# Seed_Laser_Controller.net
KiCad netlist of a schematic drawn in Altium Designer
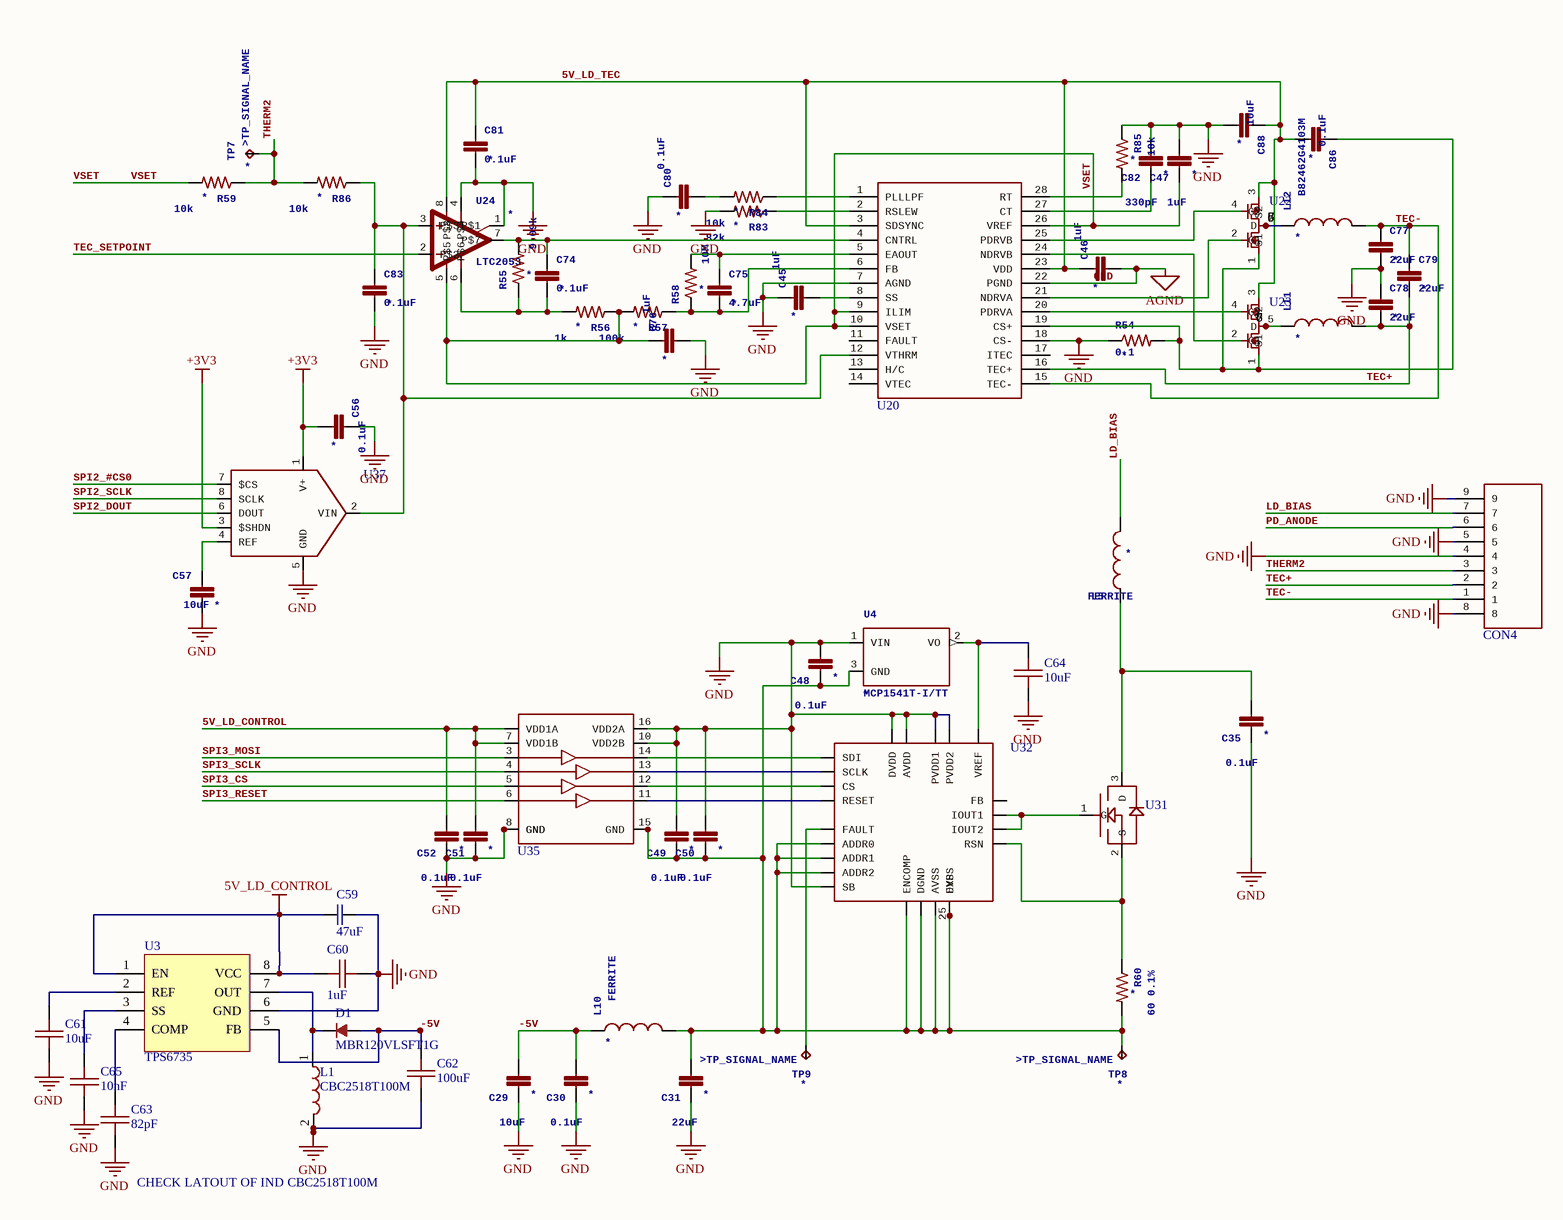
[diagram p0: Seed Laser Controller.SchDoc]

(export (version "E")
  (design (tool "Eeschema 10.0.6"))
  (components
    (comp (ref "C29")
      (value "10uF")
      (footprint "0603")
      (description "CAPACITOR, European symbol")
      (fields (field (name "NAME") "*"))
      (libsource (lib "") (part "C-EUC0603K_1"))
    )
    (comp (ref "C30")
      (value "0.1uF")
      (footprint "0603")
      (description "CAPACITOR, European symbol")
      (fields (field (name "NAME") "*"))
      (libsource (lib "") (part "C-EUC0603K_1"))
    )
    (comp (ref "C31")
      (value "22uF")
      (footprint "0603")
      (description "CAPACITOR, European symbol")
      (fields (field (name "NAME") "*"))
      (libsource (lib "") (part "C-EUC0603K_1"))
    )
    (comp (ref "C35")
      (value "0.1uF")
      (footprint "0603")
      (description "CAPACITOR, European symbol")
      (fields (field (name "NAME") "*"))
      (libsource (lib "") (part "C-EUC0603K_1"))
    )
    (comp (ref "C45")
      (value "1uF")
      (footprint "0402")
      (description "CAPACITOR, European symbol")
      (fields (field (name "NAME") "*"))
      (libsource (lib "rcl") (part "C-EUC0402"))
    )
    (comp (ref "C46")
      (value "1uF")
      (footprint "0402")
      (description "CAPACITOR, European symbol")
      (fields (field (name "NAME") "*"))
      (libsource (lib "rcl") (part "C-EUC0402"))
    )
    (comp (ref "C47")
      (value "1uF")
      (footprint "0402")
      (description "CAPACITOR, European symbol")
      (fields (field (name "NAME") "*"))
      (libsource (lib "") (part "C-EUC0402_1"))
    )
    (comp (ref "C48")
      (value "0.1uF")
      (footprint "0402 B")
      (description "CAPACITOR, European symbol")
      (fields (field (name "NAME") "*"))
      (libsource (lib "") (part "C-EUC0402_1"))
    )
    (comp (ref "C49")
      (value "0.1uF")
      (footprint "0402 B")
      (description "CAPACITOR, European symbol")
      (fields (field (name "NAME") "*"))
      (libsource (lib "") (part "C-EUC0402_1"))
    )
    (comp (ref "C50")
      (value "0.1uF")
      (footprint "0402 B")
      (description "CAPACITOR, European symbol")
      (fields (field (name "NAME") "*"))
      (libsource (lib "") (part "C-EUC0402_1"))
    )
    (comp (ref "C51")
      (value "0.1uF")
      (footprint "0402 B")
      (description "CAPACITOR, European symbol")
      (fields (field (name "NAME") "*"))
      (libsource (lib "") (part "C-EUC0402_1"))
    )
    (comp (ref "C52")
      (value "0.1uF")
      (footprint "0402 B")
      (description "CAPACITOR, European symbol")
      (fields (field (name "NAME") "*"))
      (libsource (lib "") (part "C-EUC0402_1"))
    )
    (comp (ref "C56")
      (value "0.1uF")
      (footprint "0402")
      (description "CAPACITOR, European symbol")
      (fields (field (name "NAME") "*"))
      (libsource (lib "rcl") (part "C-EUC0402K"))
    )
    (comp (ref "C57")
      (value "10uF")
      (footprint "0603")
      (description "CAPACITOR, European symbol")
      (fields (field (name "NAME") "*"))
      (libsource (lib "rcl") (part "C-EUC0603K"))
    )
    (comp (ref "C59") (value "47uF") (footprint "0603") (libsource (lib "DaughterBoard") (part "Cap 0603")))
    (comp (ref "C60")
      (value "1uF")
      (footprint "0402 B")
      (description "402 Capacitor")
      (libsource (lib "DaughterBoard") (part "CAP 0402"))
    )
    (comp (ref "C61")
      (value "10uF")
      (footprint "0402 B")
      (description "402 Capacitor")
      (libsource (lib "DaughterBoard") (part "CAP 0402"))
    )
    (comp (ref "C62")
      (value "100uF")
      (footprint "1206 B")
      (description "1206 Capacitor")
      (libsource (lib "DaughterBoard") (part "CAP 1206"))
    )
    (comp (ref "C63")
      (value "82pF")
      (footprint "0402 B")
      (description "402 Capacitor")
      (libsource (lib "DaughterBoard") (part "CAP 0402"))
    )
    (comp (ref "C64")
      (value "10uF")
      (footprint "0402 B")
      (description "402 Capacitor")
      (libsource (lib "DaughterBoard") (part "CAP 0402"))
    )
    (comp (ref "C65")
      (value "10nF")
      (footprint "0402 B")
      (description "402 Capacitor")
      (libsource (lib "DaughterBoard") (part "CAP 0402"))
    )
    (comp (ref "C74")
      (value "0.1uF")
      (footprint "0603")
      (description "CAPACITOR, European symbol")
      (fields (field (name "NAME") "*"))
      (libsource (lib "rcl") (part "C-EUC0603"))
    )
    (comp (ref "C75")
      (value "4.7uF")
      (footprint "0603")
      (description "CAPACITOR, European symbol")
      (fields (field (name "NAME") "*"))
      (libsource (lib "rcl") (part "C-EUC0603"))
    )
    (comp (ref "C76")
      (value "1uF")
      (footprint "0402")
      (description "CAPACITOR, European symbol")
      (fields (field (name "NAME") "*"))
      (libsource (lib "rcl") (part "C-EUC0402"))
    )
    (comp (ref "C77")
      (value "22uF")
      (footprint "0402")
      (description "CAPACITOR, European symbol")
      (fields (field (name "NAME") "*"))
      (libsource (lib "") (part "C-EUC0402_2"))
    )
    (comp (ref "C78")
      (value "22uF")
      (footprint "0402")
      (description "CAPACITOR, European symbol")
      (fields (field (name "NAME") "*"))
      (libsource (lib "") (part "C-EUC0402_2"))
    )
    (comp (ref "C79")
      (value "22uF")
      (footprint "0603")
      (description "CAPACITOR, European symbol")
      (fields (field (name "NAME") "*"))
      (libsource (lib "rcl") (part "C-EUC0603"))
    )
    (comp (ref "C80")
      (value "0.1uF")
      (footprint "0402")
      (description "CAPACITOR, European symbol")
      (fields (field (name "NAME") "*"))
      (libsource (lib "rcl") (part "C-EUC0402"))
    )
    (comp (ref "C81")
      (value "0.1uF")
      (footprint "0603")
      (description "CAPACITOR, European symbol")
      (fields (field (name "NAME") "*"))
      (libsource (lib "") (part "C-EUC0402_2"))
    )
    (comp (ref "C82")
      (value "330pF")
      (footprint "0402")
      (description "CAPACITOR, European symbol")
      (fields (field (name "NAME") "*"))
      (libsource (lib "") (part "C-EUC0402_1"))
    )
    (comp (ref "C83")
      (value "0.1uF")
      (footprint "0402")
      (description "CAPACITOR, European symbol")
      (fields (field (name "NAME") "*"))
      (libsource (lib "") (part "C-EUC0402_2"))
    )
    (comp (ref "C86")
      (value "0.1uF")
      (footprint "0402")
      (description "CAPACITOR, European symbol")
      (fields (field (name "NAME") "*"))
      (libsource (lib "") (part "C-EUC0402_3"))
    )
    (comp (ref "C88")
      (value "10uF")
      (footprint "0603")
      (description "CAPACITOR, European symbol")
      (fields (field (name "NAME") "*"))
      (libsource (lib "rcl") (part "C-EUC0603K"))
    )
    (comp (ref "CON4")
      (value "SAMTEC_T1M_X7")
      (footprint "T1M-07-F-SH-L-K")
      (libsource (lib "custom") (part "SAMTEC_T1M_X7"))
    )
    (comp (ref "D1")
      (value "MBR120VLSFT1G")
      (footprint "SOD123FL")
      (description "DIODE SCHOTTKY 20V 1A")
      (libsource (lib "DaughterBoard") (part "MBR120VLSFT1G"))
    )
    (comp (ref "L1")
      (value "CBC2518T100M")
      (footprint "1007")
      (libsource (lib "DaughterBoard") (part "CBC2518T100M"))
    )
    (comp (ref "L5")
      (value "FERRITE")
      (footprint "0603R")
      (fields (field (name "NAME") "*"))
      (libsource (lib "SparkFun-Passives") (part "INDUCTOR0603"))
    )
    (comp (ref "L10")
      (value "FERRITE")
      (footprint "0603R")
      (fields (field (name "NAME") "*"))
      (libsource (lib "SparkFun-Passives") (part "INDUCTOR0603"))
    )
    (comp (ref "L11")
      (value "B82462G4103M")
      (footprint "B82462G")
      (description "10uH")
      (fields (field (name "NAME") "*"))
      (libsource (lib "SparkFun-Passives") (part "INDUCTOR-B82462G"))
    )
    (comp (ref "L12")
      (value "B82462G4103M")
      (footprint "B82462G")
      (description "10uH")
      (fields (field (name "NAME") "*"))
      (libsource (lib "SparkFun-Passives") (part "INDUCTOR-B82462G"))
    )
    (comp (ref "R54")
      (value "0.1")
      (footprint "1206R")
      (description "RESISTOR, American symbol")
      (fields (field (name "NAME") "*"))
      (libsource (lib "rcl") (part "R-US_R1206"))
    )
    (comp (ref "R55")
      (value "9.09k")
      (footprint "0603R")
      (description "RESISTOR, American symbol")
      (fields (field (name "NAME") "*"))
      (libsource (lib "rcl") (part "R-US_R0603"))
    )
    (comp (ref "R56")
      (value "1k")
      (footprint "0603R")
      (description "RESISTOR, American symbol")
      (fields (field (name "NAME") "*"))
      (libsource (lib "rcl") (part "R-US_R0603"))
    )
    (comp (ref "R57")
      (value "100k")
      (footprint "0603R")
      (description "RESISTOR, American symbol")
      (fields (field (name "NAME") "*"))
      (libsource (lib "rcl") (part "R-US_R0603"))
    )
    (comp (ref "R58")
      (value "10M")
      (footprint "0603R")
      (description "RESISTOR, American symbol")
      (fields (field (name "NAME") "*"))
      (libsource (lib "rcl") (part "R-US_R0603"))
    )
    (comp (ref "R59")
      (value "10k")
      (footprint "0603R")
      (description "RESISTOR, American symbol")
      (fields (field (name "NAME") "*"))
      (libsource (lib "rcl") (part "R-US_R0603"))
    )
    (comp (ref "R60")
      (value "60 0.1%")
      (footprint "0603R")
      (description "RESISTOR, American symbol")
      (fields (field (name "NAME") "*"))
      (libsource (lib "rcl") (part "R-US_R0603"))
    )
    (comp (ref "R83")
      (value "82k")
      (footprint "0402R")
      (description "RESISTOR, American symbol")
      (fields (field (name "NAME") "*"))
      (libsource (lib "rcl") (part "R-US_R0402"))
    )
    (comp (ref "R84")
      (value "10k")
      (footprint "0402R")
      (description "RESISTOR, American symbol")
      (fields (field (name "NAME") "*"))
      (libsource (lib "rcl") (part "R-US_R0402"))
    )
    (comp (ref "R85")
      (value "10k")
      (footprint "0402R")
      (description "RESISTOR, American symbol")
      (fields (field (name "NAME") "*"))
      (libsource (lib "rcl") (part "R-US_R0402"))
    )
    (comp (ref "R86")
      (value "10k")
      (footprint "0603R")
      (description "RESISTOR, American symbol")
      (fields (field (name "NAME") "*"))
      (libsource (lib "rcl") (part "R-US_R0603"))
    )
    (comp (ref "TP7")
      (value "TPB1,27")
      (footprint "B1,27")
      (description "Test pad")
      (fields
        (field (name "NAME") "*")
        (field (name "TP_SIGNAL_NAME") ">TP_SIGNAL_NAME")
        (field (name "LIBRARYNAME") "testpad")
      )
      (libsource (lib "testpad") (part "TPB1,27"))
    )
    (comp (ref "TP8")
      (value "TPB1,27")
      (footprint "B1,27")
      (description "Test pad")
      (fields
        (field (name "NAME") "*")
        (field (name "TP_SIGNAL_NAME") ">TP_SIGNAL_NAME")
        (field (name "LIBRARYNAME") "testpad")
      )
      (libsource (lib "testpad") (part "TPB1,27"))
    )
    (comp (ref "TP9")
      (value "TPB1,27")
      (footprint "B1,27")
      (description "Test pad")
      (fields
        (field (name "NAME") "*")
        (field (name "TP_SIGNAL_NAME") ">TP_SIGNAL_NAME")
        (field (name "LIBRARYNAME") "testpad")
      )
      (libsource (lib "testpad") (part "TPB1,27"))
    )
    (comp (ref "U3") (value "TPS6735") (footprint "SOIC8") (libsource (lib "DaughterBoard") (part "TPS6735")))
    (comp (ref "U4")
      (value "MCP1541T-I/TT")
      (footprint "SOT-23")
      (description "2.5V and 4.096V Voltage ReferencesSource: http://www.microchip.com .. 21653b.pdf")
      (fields (field (name "NAME") "*"))
      (libsource (lib "microchip") (part "MC15*TT"))
    )
    (comp (ref "U20")
      (value "LTC1923SSOP28")
      (footprint "SSOP-28")
      (libsource (lib "custom") (part "LTC1923SSOP28"))
    )
    (comp (ref "U22") (value "SI9801DY") (footprint "SOIC8") (libsource (lib "custom") (part "SI9801DY")))
    (comp (ref "U23") (value "SI9801DY") (footprint "SOIC8") (libsource (lib "custom") (part "SI9801DY")))
    (comp (ref "U24")
      (value "LTC2053")
      (footprint "MSOP8")
      (fields (field (name "NAME") "*"))
      (libsource (lib "custom") (part "LTC2053"))
    )
    (comp (ref "U31") (value "SI2334DS") (footprint "SOT-23") (libsource (lib "custom") (part "SI2334DS")))
    (comp (ref "U32")
      (value "ADN8810ACPZ")
      (footprint "LFCSP-24")
      (libsource (lib "custom") (part "ADN8810"))
    )
    (comp (ref "U35") (value "ADUM7440") (footprint "QSOP16") (libsource (lib "custom") (part "ADUM7440")))
    (comp (ref "U37") (value "MAX1240") (footprint "SOIC8") (libsource (lib "custom") (part "MAX1240")))
  )
  (nets
    (net (code "1") (name "+3V3") (class "Default")
      (node (ref "C56") (pin "2") (pinfunction "2_2") (pintype "passive"))
      (node (ref "U37") (pin "1") (pinfunction "V+_1") (pintype "passive"))
      (node (ref "U37") (pin "3") (pinfunction "$SHDN_3") (pintype "passive"))
    )
    (net (code "2") (name "/-5V") (class "Default")
      (node (ref "C29") (pin "2") (pinfunction "2_2") (pintype "passive"))
      (node (ref "C30") (pin "2") (pinfunction "2_2") (pintype "passive"))
      (node (ref "C62") (pin "2") (pintype "passive"))
      (node (ref "D1") (pin "2") (pinfunction "A_2") (pintype "passive"))
      (node (ref "L10") (pin "1") (pinfunction "1_1") (pintype "passive"))
      (node (ref "U3") (pin "5") (pinfunction "FB_5") (pintype "passive"))
    )
    (net (code "3") (name "/5V_LD_TEC") (class "Default")
      (node (ref "C46") (pin "1") (pinfunction "1_1") (pintype "passive"))
      (node (ref "C81") (pin "1") (pinfunction "1_1") (pintype "passive"))
      (node (ref "C86") (pin "2") (pinfunction "2_2") (pintype "passive"))
      (node (ref "C88") (pin "1") (pinfunction "1_1") (pintype "passive"))
      (node (ref "U20") (pin "23") (pinfunction "VDD_23") (pintype "passive"))
      (node (ref "U20") (pin "3") (pinfunction "SDSYNC_3") (pintype "passive"))
      (node (ref "U22") (pin "3") (pinfunction "S2_3") (pintype "passive"))
      (node (ref "U23") (pin "3") (pinfunction "S2_3") (pintype "passive"))
      (node (ref "U24") (pin "8") (pinfunction "P$8_8") (pintype "passive"))
    )
    (net (code "4") (name "/LD_BIAS") (class "Default")
      (node (ref "CON4") (pin "7") (pinfunction "7_7") (pintype "passive"))
      (node (ref "L5") (pin "2") (pinfunction "2_2") (pintype "passive"))
    )
    (net (code "5") (name "/PD_ANODE") (class "Default")
      (node (ref "CON4") (pin "6") (pinfunction "6_6") (pintype "passive"))
    )
    (net (code "6") (name "/SPI2_#CS0") (class "Default")
      (node (ref "U37") (pin "7") (pinfunction "$CS_7") (pintype "passive"))
    )
    (net (code "7") (name "/SPI2_DOUT") (class "Default")
      (node (ref "U37") (pin "6") (pinfunction "DOUT_6") (pintype "passive"))
    )
    (net (code "8") (name "/SPI2_SCLK") (class "Default")
      (node (ref "U37") (pin "8") (pinfunction "SCLK_8") (pintype "passive"))
    )
    (net (code "9") (name "/SPI3_CS") (class "Default")
      (node (ref "U35") (pin "5") (pinfunction "P$5_5") (pintype "passive"))
    )
    (net (code "10") (name "/SPI3_MOSI") (class "Default")
      (node (ref "U35") (pin "3") (pinfunction "P$3_3") (pintype "passive"))
    )
    (net (code "11") (name "/SPI3_RESET") (class "Default")
      (node (ref "U35") (pin "6") (pinfunction "P$6_6") (pintype "passive"))
    )
    (net (code "12") (name "/SPI3_SCLK") (class "Default")
      (node (ref "U35") (pin "4") (pinfunction "P$4_4") (pintype "passive"))
    )
    (net (code "13") (name "/TEC+") (class "Default")
      (node (ref "C78") (pin "2") (pinfunction "2_2") (pintype "passive"))
      (node (ref "C79") (pin "2") (pinfunction "2_2") (pintype "passive"))
      (node (ref "CON4") (pin "2") (pinfunction "2_2") (pintype "passive"))
      (node (ref "L11") (pin "P$2") (pinfunction "2_P$2") (pintype "passive"))
      (node (ref "U20") (pin "16") (pinfunction "TEC+_16") (pintype "passive"))
    )
    (net (code "14") (name "/TEC-") (class "Default")
      (node (ref "C77") (pin "1") (pinfunction "1_1") (pintype "passive"))
      (node (ref "C79") (pin "1") (pinfunction "1_1") (pintype "passive"))
      (node (ref "CON4") (pin "1") (pinfunction "1_1") (pintype "passive"))
      (node (ref "L12") (pin "P$2") (pinfunction "2_P$2") (pintype "passive"))
      (node (ref "U20") (pin "15") (pinfunction "TEC-_15") (pintype "passive"))
    )
    (net (code "15") (name "/TEC_SETPOINT") (class "Default")
      (node (ref "U24") (pin "2") (pinfunction "P$2_2") (pintype "passive"))
    )
    (net (code "16") (name "/THERM2") (class "Default")
      (node (ref "CON4") (pin "3") (pinfunction "3_3") (pintype "passive"))
      (node (ref "R59") (pin "1") (pinfunction "1_1") (pintype "passive"))
      (node (ref "R86") (pin "2") (pinfunction "2_2") (pintype "passive"))
      (node (ref "TP7") (pin "TP") (pinfunction "TP_TP") (pintype "passive"))
    )
    (net (code "17") (name "/VSET") (class "Default")
      (node (ref "C47") (pin "1") (pinfunction "1_1") (pintype "passive"))
      (node (ref "C76") (pin "1") (pinfunction "1_1") (pintype "passive"))
      (node (ref "R56") (pin "1") (pinfunction "1_1") (pintype "passive"))
      (node (ref "R57") (pin "2") (pinfunction "2_2") (pintype "passive"))
      (node (ref "R59") (pin "2") (pinfunction "2_2") (pintype "passive"))
      (node (ref "U20") (pin "10") (pinfunction "VSET_10") (pintype "passive"))
      (node (ref "U20") (pin "26") (pinfunction "VREF_26") (pintype "passive"))
      (node (ref "U20") (pin "9") (pinfunction "ILIM_9") (pintype "passive"))
      (node (ref "U24") (pin "5") (pinfunction "P$5_5") (pintype "passive"))
    )
    (net (code "18") (name "5V_LD_CONTROL") (class "Default")
      (node (ref "C51") (pin "2") (pinfunction "2_2") (pintype "passive"))
      (node (ref "C52") (pin "2") (pinfunction "2_2") (pintype "passive"))
      (node (ref "C59") (pin "1") (pinfunction "1_1") (pintype "passive"))
      (node (ref "C60") (pin "2") (pintype "passive"))
      (node (ref "U3") (pin "1") (pinfunction "EN_1") (pintype "passive"))
      (node (ref "U3") (pin "8") (pinfunction "VCC_8") (pintype "passive"))
      (node (ref "U35") (pin "1") (pinfunction "VDD1A_1") (pintype "passive"))
      (node (ref "U35") (pin "7") (pinfunction "VDD1B_7") (pintype "passive"))
    )
    (net (code "19") (name "AGND") (class "Default")
      (node (ref "C29") (pin "1") (pinfunction "1_1") (pintype "passive"))
      (node (ref "C30") (pin "1") (pinfunction "1_1") (pintype "passive"))
      (node (ref "C31") (pin "1") (pinfunction "1_1") (pintype "passive"))
      (node (ref "C35") (pin "1") (pinfunction "1_1") (pintype "passive"))
      (node (ref "C45") (pin "1") (pinfunction "1_1") (pintype "passive"))
      (node (ref "C46") (pin "2") (pinfunction "2_2") (pintype "passive"))
      (node (ref "C47") (pin "2") (pinfunction "2_2") (pintype "passive"))
      (node (ref "C48") (pin "2") (pinfunction "2_2") (pintype "passive"))
      (node (ref "C49") (pin "2") (pinfunction "2_2") (pintype "passive"))
      (node (ref "C50") (pin "2") (pinfunction "2_2") (pintype "passive"))
      (node (ref "C51") (pin "1") (pinfunction "1_1") (pintype "passive"))
      (node (ref "C52") (pin "1") (pinfunction "1_1") (pintype "passive"))
      (node (ref "C56") (pin "1") (pinfunction "1_1") (pintype "passive"))
      (node (ref "C57") (pin "2") (pinfunction "2_2") (pintype "passive"))
      (node (ref "C59") (pin "2") (pinfunction "2_2") (pintype "passive"))
      (node (ref "C60") (pin "1") (pintype "passive"))
      (node (ref "C61") (pin "1") (pintype "passive"))
      (node (ref "C62") (pin "1") (pintype "passive"))
      (node (ref "C63") (pin "1") (pintype "passive"))
      (node (ref "C64") (pin "1") (pintype "passive"))
      (node (ref "C65") (pin "1") (pintype "passive"))
      (node (ref "C76") (pin "2") (pinfunction "2_2") (pintype "passive"))
      (node (ref "C77") (pin "2") (pinfunction "2_2") (pintype "passive"))
      (node (ref "C78") (pin "1") (pinfunction "1_1") (pintype "passive"))
      (node (ref "C80") (pin "1") (pinfunction "1_1") (pintype "passive"))
      (node (ref "C81") (pin "2") (pinfunction "2_2") (pintype "passive"))
      (node (ref "C82") (pin "2") (pinfunction "2_2") (pintype "passive"))
      (node (ref "C83") (pin "2") (pinfunction "2_2") (pintype "passive"))
      (node (ref "C88") (pin "2") (pinfunction "2_2") (pintype "passive"))
      (node (ref "CON4") (pin "4") (pinfunction "4_4") (pintype "passive"))
      (node (ref "CON4") (pin "5") (pinfunction "5_5") (pintype "passive"))
      (node (ref "CON4") (pin "8") (pinfunction "8_8") (pintype "passive"))
      (node (ref "CON4") (pin "9") (pinfunction "9_9") (pintype "passive"))
      (node (ref "L1") (pin "2") (pinfunction "2_2") (pintype "passive"))
      (node (ref "R54") (pin "1") (pinfunction "1_1") (pintype "passive"))
      (node (ref "R83") (pin "2") (pinfunction "2_2") (pintype "passive"))
      (node (ref "R85") (pin "1") (pinfunction "1_1") (pintype "passive"))
      (node (ref "U20") (pin "18") (pinfunction "CS-_18") (pintype "passive"))
      (node (ref "U20") (pin "22") (pinfunction "PGND_22") (pintype "passive"))
      (node (ref "U20") (pin "7") (pinfunction "AGND_7") (pintype "passive"))
      (node (ref "U24") (pin "1") (pinfunction "P$1_1") (pintype "passive"))
      (node (ref "U24") (pin "4") (pinfunction "P$4_4") (pintype "passive"))
      (node (ref "U3") (pin "6") (pinfunction "GND_6") (pintype "passive"))
      (node (ref "U32") (pin "11") (pinfunction "PVDD2_11") (pintype "passive"))
      (node (ref "U32") (pin "15") (pinfunction "AVDD_15") (pintype "passive"))
      (node (ref "U32") (pin "23") (pinfunction "DVDD_23") (pintype "passive"))
      (node (ref "U32") (pin "7") (pinfunction "SB_7") (pintype "passive"))
      (node (ref "U32") (pin "8") (pinfunction "PVDD1_8") (pintype "passive"))
      (node (ref "U35") (pin "10") (pinfunction "VDD2B_10") (pintype "passive"))
      (node (ref "U35") (pin "16") (pinfunction "VDD2A_16") (pintype "passive"))
      (node (ref "U35") (pin "2") (pinfunction "GND_2") (pintype "passive"))
      (node (ref "U35") (pin "8") (pinfunction "GND_8") (pintype "passive"))
      (node (ref "U37") (pin "5") (pinfunction "GND_5") (pintype "passive"))
      (node (ref "U4") (pin "1") (pinfunction "VIN_1") (pintype "passive"))
    )
    (net (code "20") (name "Net-(C80-Pad2)") (class "Default")
      (node (ref "C80") (pin "2") (pinfunction "2_2") (pintype "passive"))
      (node (ref "R84") (pin "2") (pinfunction "2_2") (pintype "passive"))
    )
    (net (code "21") (name "Net-(D1-K)") (class "Default")
      (node (ref "D1") (pin "1") (pinfunction "K_1") (pintype "passive"))
      (node (ref "L1") (pin "1") (pinfunction "1_1") (pintype "passive"))
      (node (ref "U3") (pin "7") (pinfunction "OUT_7") (pintype "passive"))
    )
    (net (code "22") (name "Net-(L11-1)") (class "Default")
      (node (ref "L11") (pin "P$1") (pinfunction "1_P$1") (pintype "passive"))
      (node (ref "U23") (pin "5") (pinfunction "D_5") (pintype "passive"))
      (node (ref "U23") (pin "6") (pinfunction "D_6") (pintype "passive"))
      (node (ref "U23") (pin "7") (pinfunction "D_7") (pintype "passive"))
      (node (ref "U23") (pin "8") (pinfunction "D_8") (pintype "passive"))
    )
    (net (code "23") (name "Net-(L12-1)") (class "Default")
      (node (ref "L12") (pin "P$1") (pinfunction "1_P$1") (pintype "passive"))
      (node (ref "U22") (pin "5") (pinfunction "D_5") (pintype "passive"))
      (node (ref "U22") (pin "6") (pinfunction "D_6") (pintype "passive"))
      (node (ref "U22") (pin "7") (pinfunction "D_7") (pintype "passive"))
      (node (ref "U22") (pin "8") (pinfunction "D_8") (pintype "passive"))
    )
    (net (code "24") (name "Net-(U3-COMP)") (class "Default")
      (node (ref "C63") (pin "2") (pintype "passive"))
      (node (ref "U3") (pin "4") (pinfunction "COMP_4") (pintype "passive"))
    )
    (net (code "25") (name "Net-(U3-REF)") (class "Default")
      (node (ref "C61") (pin "2") (pintype "passive"))
      (node (ref "U3") (pin "2") (pinfunction "REF_2") (pintype "passive"))
    )
    (net (code "26") (name "Net-(U3-SS)") (class "Default")
      (node (ref "C65") (pin "2") (pintype "passive"))
      (node (ref "U3") (pin "3") (pinfunction "SS_3") (pintype "passive"))
    )
    (net (code "27") (name "Net-(U20-CNTRL)") (class "Default")
      (node (ref "C74") (pin "1") (pinfunction "1_1") (pintype "passive"))
      (node (ref "R55") (pin "2") (pinfunction "2_2") (pintype "passive"))
      (node (ref "U20") (pin "4") (pinfunction "CNTRL_4") (pintype "passive"))
      (node (ref "U24") (pin "7") (pinfunction "P$7_7") (pintype "passive"))
    )
    (net (code "28") (name "Net-(U20-CS+)") (class "Default")
      (node (ref "C86") (pin "1") (pinfunction "1_1") (pintype "passive"))
      (node (ref "R54") (pin "2") (pinfunction "2_2") (pintype "passive"))
      (node (ref "U20") (pin "19") (pinfunction "CS+_19") (pintype "passive"))
      (node (ref "U22") (pin "1") (pinfunction "S1_1") (pintype "passive"))
      (node (ref "U23") (pin "1") (pinfunction "S1_1") (pintype "passive"))
    )
    (net (code "29") (name "Net-(U20-CT)") (class "Default")
      (node (ref "C82") (pin "1") (pinfunction "1_1") (pintype "passive"))
      (node (ref "U20") (pin "27") (pinfunction "CT_27") (pintype "passive"))
    )
    (net (code "30") (name "Net-(U20-EAOUT)") (class "Default")
      (node (ref "C75") (pin "1") (pinfunction "1_1") (pintype "passive"))
      (node (ref "R58") (pin "2") (pinfunction "2_2") (pintype "passive"))
      (node (ref "U20") (pin "5") (pinfunction "EAOUT_5") (pintype "passive"))
    )
    (net (code "31") (name "Net-(U20-FB)") (class "Default")
      (node (ref "C75") (pin "2") (pinfunction "2_2") (pintype "passive"))
      (node (ref "R57") (pin "1") (pinfunction "1_1") (pintype "passive"))
      (node (ref "R58") (pin "1") (pinfunction "1_1") (pintype "passive"))
      (node (ref "U20") (pin "6") (pinfunction "FB_6") (pintype "passive"))
    )
    (net (code "32") (name "Net-(U20-NDRVA)") (class "Default")
      (node (ref "U20") (pin "21") (pinfunction "NDRVA_21") (pintype "passive"))
      (node (ref "U22") (pin "2") (pinfunction "G1_2") (pintype "passive"))
    )
    (net (code "33") (name "Net-(U20-NDRVB)") (class "Default")
      (node (ref "U20") (pin "24") (pinfunction "NDRVB_24") (pintype "passive"))
      (node (ref "U23") (pin "2") (pinfunction "G1_2") (pintype "passive"))
    )
    (net (code "34") (name "Net-(U20-PDRVA)") (class "Default")
      (node (ref "U20") (pin "20") (pinfunction "PDRVA_20") (pintype "passive"))
      (node (ref "U23") (pin "4") (pinfunction "G2_4") (pintype "passive"))
    )
    (net (code "35") (name "Net-(U20-PDRVB)") (class "Default")
      (node (ref "U20") (pin "25") (pinfunction "PDRVB_25") (pintype "passive"))
      (node (ref "U22") (pin "4") (pinfunction "G2_4") (pintype "passive"))
    )
    (net (code "36") (name "Net-(U20-PLLLPF)") (class "Default")
      (node (ref "R84") (pin "1") (pinfunction "1_1") (pintype "passive"))
      (node (ref "U20") (pin "1") (pinfunction "PLLLPF_1") (pintype "passive"))
    )
    (net (code "37") (name "Net-(U20-RSLEW)") (class "Default")
      (node (ref "R83") (pin "1") (pinfunction "1_1") (pintype "passive"))
      (node (ref "U20") (pin "2") (pinfunction "RSLEW_2") (pintype "passive"))
    )
    (net (code "38") (name "Net-(U20-RT)") (class "Default")
      (node (ref "R85") (pin "2") (pinfunction "2_2") (pintype "passive"))
      (node (ref "U20") (pin "28") (pinfunction "RT_28") (pintype "passive"))
    )
    (net (code "39") (name "Net-(U20-SS)") (class "Default")
      (node (ref "C45") (pin "2") (pinfunction "2_2") (pintype "passive"))
      (node (ref "U20") (pin "8") (pinfunction "SS_8") (pintype "passive"))
    )
    (net (code "40") (name "Net-(U20-VTHRM)") (class "Default")
      (node (ref "C83") (pin "1") (pinfunction "1_1") (pintype "passive"))
      (node (ref "R86") (pin "1") (pinfunction "1_1") (pintype "passive"))
      (node (ref "U20") (pin "12") (pinfunction "VTHRM_12") (pintype "passive"))
      (node (ref "U24") (pin "3") (pinfunction "P$3_3") (pintype "passive"))
      (node (ref "U37") (pin "2") (pinfunction "VIN_2") (pintype "passive"))
    )
    (net (code "41") (name "Net-(U24-P$6)") (class "Default")
      (node (ref "C74") (pin "2") (pinfunction "2_2") (pintype "passive"))
      (node (ref "R55") (pin "1") (pinfunction "1_1") (pintype "passive"))
      (node (ref "R56") (pin "2") (pinfunction "2_2") (pintype "passive"))
      (node (ref "U24") (pin "6") (pinfunction "P$6_6") (pintype "passive"))
    )
    (net (code "42") (name "Net-(U31-D)") (class "Default")
      (node (ref "C35") (pin "2") (pinfunction "2_2") (pintype "passive"))
      (node (ref "L5") (pin "1") (pinfunction "1_1") (pintype "passive"))
      (node (ref "U31") (pin "3") (pinfunction "D_3") (pintype "passive"))
    )
    (net (code "43") (name "Net-(U31-G)") (class "Default")
      (node (ref "U31") (pin "1") (pinfunction "G_1") (pintype "passive"))
      (node (ref "U32") (pin "10") (pinfunction "IOUT2_10") (pintype "passive"))
      (node (ref "U32") (pin "9") (pinfunction "IOUT1_9") (pintype "passive"))
    )
    (net (code "44") (name "Net-(U31-S)") (class "Default")
      (node (ref "R60") (pin "1") (pinfunction "1_1") (pintype "passive"))
      (node (ref "U31") (pin "2") (pinfunction "S_2") (pintype "passive"))
      (node (ref "U32") (pin "2") (pinfunction "RSN_2") (pintype "passive"))
    )
    (net (code "45") (name "Net-(U32-ADDR0)") (class "Default")
      (node (ref "C31") (pin "2") (pinfunction "2_2") (pintype "passive"))
      (node (ref "C48") (pin "1") (pinfunction "1_1") (pintype "passive"))
      (node (ref "C49") (pin "1") (pinfunction "1_1") (pintype "passive"))
      (node (ref "C50") (pin "1") (pinfunction "1_1") (pintype "passive"))
      (node (ref "L10") (pin "2") (pinfunction "2_2") (pintype "passive"))
      (node (ref "R60") (pin "2") (pinfunction "2_2") (pintype "passive"))
      (node (ref "TP8") (pin "TP") (pinfunction "TP_TP") (pintype "passive"))
      (node (ref "U32") (pin "1") (pinfunction "ADDR2_1") (pintype "passive"))
      (node (ref "U32") (pin "12") (pinfunction "ENCOMP_12") (pintype "passive"))
      (node (ref "U32") (pin "16") (pinfunction "AVSS_16") (pintype "passive"))
      (node (ref "U32") (pin "18") (pinfunction "DVSS_18") (pintype "passive"))
      (node (ref "U32") (pin "24") (pinfunction "DGND_24") (pintype "passive"))
      (node (ref "U32") (pin "25") (pinfunction "EXP_25") (pintype "passive"))
      (node (ref "U32") (pin "4") (pinfunction "ADDR1_4") (pintype "passive"))
      (node (ref "U32") (pin "5") (pinfunction "ADDR0_5") (pintype "passive"))
      (node (ref "U35") (pin "15") (pinfunction "GND_15") (pintype "passive"))
      (node (ref "U35") (pin "9") (pinfunction "GND_9") (pintype "passive"))
      (node (ref "U4") (pin "3") (pinfunction "GND_3") (pintype "passive"))
    )
    (net (code "46") (name "Net-(U32-CS)") (class "Default")
      (node (ref "U32") (pin "21") (pinfunction "CS_21") (pintype "passive"))
      (node (ref "U35") (pin "12") (pinfunction "P$12_12") (pintype "passive"))
    )
    (net (code "47") (name "Net-(U32-FAULT)") (class "Default")
      (node (ref "TP9") (pin "TP") (pinfunction "TP_TP") (pintype "passive"))
      (node (ref "U32") (pin "6") (pinfunction "FAULT_6") (pintype "passive"))
    )
    (net (code "48") (name "Net-(U32-RESET)") (class "Default")
      (node (ref "U32") (pin "22") (pinfunction "RESET_22") (pintype "passive"))
      (node (ref "U35") (pin "11") (pinfunction "P$11_11") (pintype "passive"))
    )
    (net (code "49") (name "Net-(U32-SCLK)") (class "Default")
      (node (ref "U32") (pin "20") (pinfunction "SCLK_20") (pintype "passive"))
      (node (ref "U35") (pin "13") (pinfunction "P$13_13") (pintype "passive"))
    )
    (net (code "50") (name "Net-(U32-SDI)") (class "Default")
      (node (ref "U32") (pin "19") (pinfunction "SDI_19") (pintype "passive"))
      (node (ref "U35") (pin "14") (pinfunction "P$14_14") (pintype "passive"))
    )
    (net (code "51") (name "Net-(U32-VREF)") (class "Default")
      (node (ref "C64") (pin "2") (pintype "passive"))
      (node (ref "U32") (pin "14") (pinfunction "VREF_14") (pintype "passive"))
      (node (ref "U4") (pin "2") (pinfunction "VO_2") (pintype "output"))
    )
    (net (code "52") (name "Net-(U37-REF)") (class "Default")
      (node (ref "C57") (pin "1") (pinfunction "1_1") (pintype "passive"))
      (node (ref "U37") (pin "4") (pinfunction "REF_4") (pintype "passive"))
    )
    (net (code "53") (name "unconnected-(U20-FAULT-Pad11)") (class "Default")
      (node (ref "U20") (pin "11") (pinfunction "FAULT_11") (pintype "passive"))
    )
    (net (code "54") (name "unconnected-(U20-H{slash}C-Pad13)") (class "Default")
      (node (ref "U20") (pin "13") (pinfunction "H/C_13") (pintype "passive"))
    )
    (net (code "55") (name "unconnected-(U20-ITEC-Pad17)") (class "Default")
      (node (ref "U20") (pin "17") (pinfunction "ITEC_17") (pintype "passive"))
    )
    (net (code "56") (name "unconnected-(U20-VTEC-Pad14)") (class "Default")
      (node (ref "U20") (pin "14") (pinfunction "VTEC_14") (pintype "passive"))
    )
    (net (code "57") (name "unconnected-(U32-FB-Pad3)") (class "Default")
      (node (ref "U32") (pin "3") (pinfunction "FB_3") (pintype "passive"))
    )
  )
)
